# Teensy3.net
KiCad netlist of a schematic drawn in Altium Designer
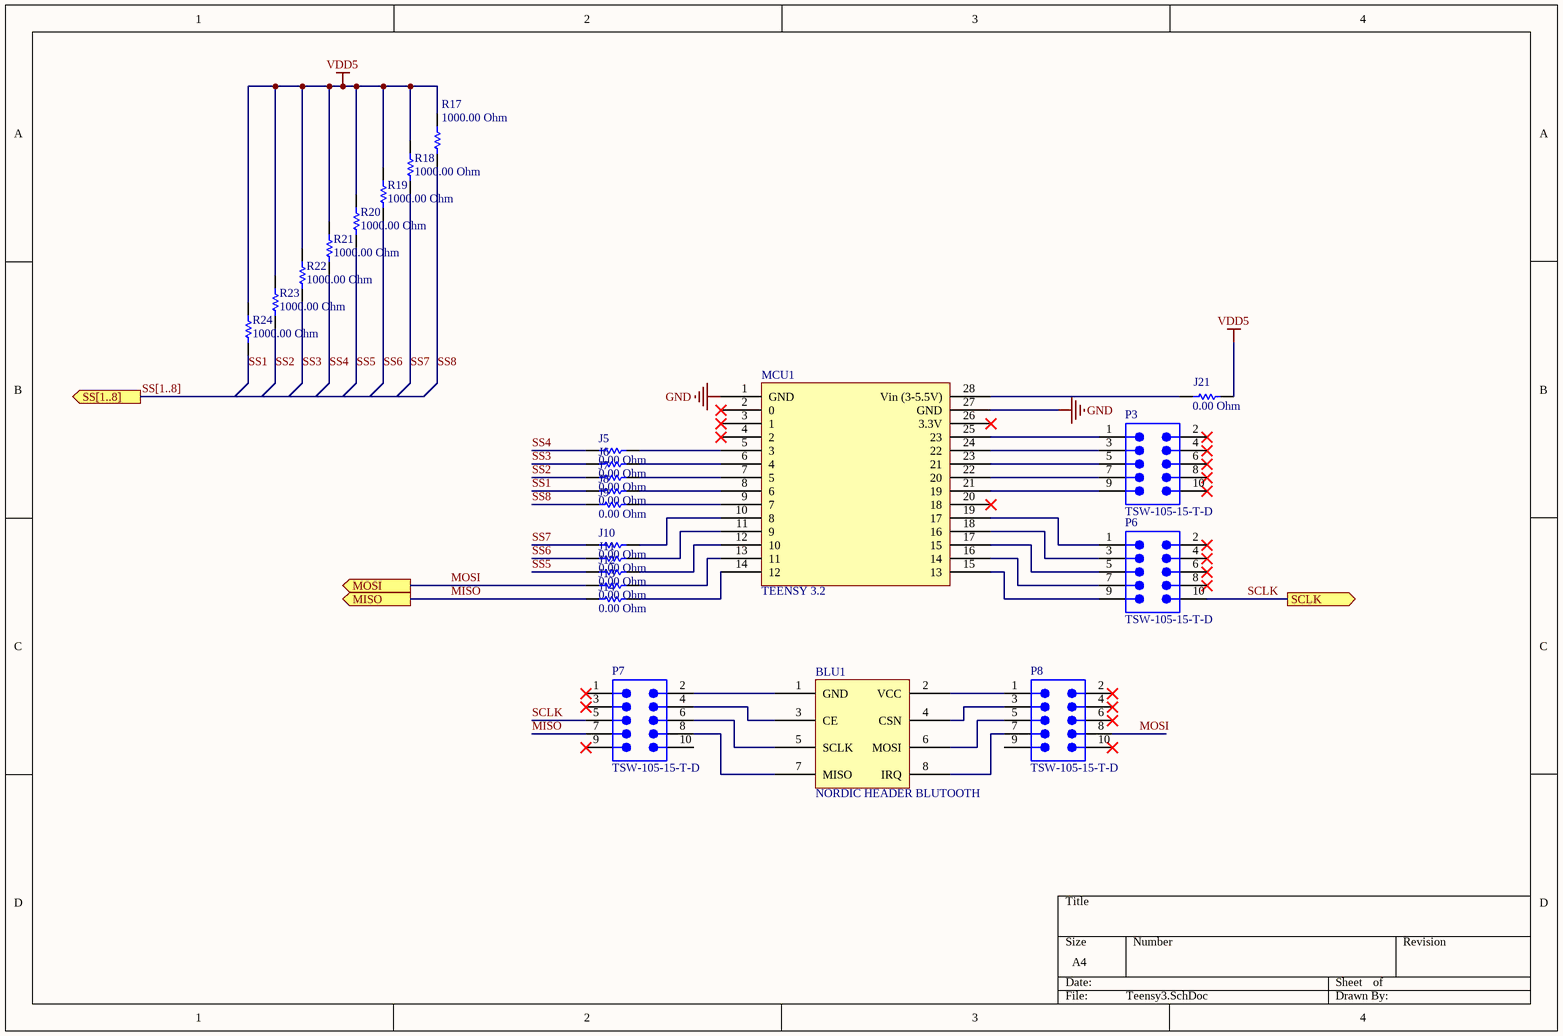
[diagram p0: Teensy3.SchDoc]

(export (version "E")
  (design (tool "Eeschema 10.0.6"))
  (components
    (comp (ref "BLU1")
      (value "NORDIC HEADER BLUTOOTH")
      (footprint "NORDIC BLUTOOTH HEADER")
      (description "BLUTOOTH MODULE")
      (fields (field (name "PUBLISHER") "Altium Limited"))
      (libsource (lib "AnserEMT") (part "NORDIC HEADER BLUTOOTH"))
    )
    (comp (ref "J5")
      (value "0.00 Ohm")
      (footprint "RESC1206(3216)_M")
      (description "Jumper 1206 (3216 Metric)")
      (fields (field (name "TOLERANCE") "None"))
      (libsource (lib "Altium Content Vault") (part "CMP-1014-00001-1"))
    )
    (comp (ref "J6")
      (value "0.00 Ohm")
      (footprint "RESC1206(3216)_M")
      (description "Jumper 1206 (3216 Metric)")
      (fields (field (name "TOLERANCE") "None"))
      (libsource (lib "Altium Content Vault") (part "CMP-1014-00001-1"))
    )
    (comp (ref "J7")
      (value "0.00 Ohm")
      (footprint "RESC1206(3216)_M")
      (description "Jumper 1206 (3216 Metric)")
      (fields (field (name "TOLERANCE") "None"))
      (libsource (lib "Altium Content Vault") (part "CMP-1014-00001-1"))
    )
    (comp (ref "J8")
      (value "0.00 Ohm")
      (footprint "RESC1206(3216)_M")
      (description "Jumper 1206 (3216 Metric)")
      (fields (field (name "TOLERANCE") "None"))
      (libsource (lib "Altium Content Vault") (part "CMP-1014-00001-1"))
    )
    (comp (ref "J9")
      (value "0.00 Ohm")
      (footprint "RESC1206(3216)_M")
      (description "Jumper 1206 (3216 Metric)")
      (fields (field (name "TOLERANCE") "None"))
      (libsource (lib "Altium Content Vault") (part "CMP-1014-00001-1"))
    )
    (comp (ref "J10")
      (value "0.00 Ohm")
      (footprint "RESC1206(3216)_M")
      (description "Jumper 1206 (3216 Metric)")
      (fields (field (name "TOLERANCE") "None"))
      (libsource (lib "Altium Content Vault") (part "CMP-1014-00001-1"))
    )
    (comp (ref "J11")
      (value "0.00 Ohm")
      (footprint "RESC1206(3216)_M")
      (description "Jumper 1206 (3216 Metric)")
      (fields (field (name "TOLERANCE") "None"))
      (libsource (lib "Altium Content Vault") (part "CMP-1014-00001-1"))
    )
    (comp (ref "J12")
      (value "0.00 Ohm")
      (footprint "RESC1206(3216)_M")
      (description "Jumper 1206 (3216 Metric)")
      (fields (field (name "TOLERANCE") "None"))
      (libsource (lib "Altium Content Vault") (part "CMP-1014-00001-1"))
    )
    (comp (ref "J13")
      (value "0.00 Ohm")
      (footprint "RESC1206(3216)_M")
      (description "Jumper 1206 (3216 Metric)")
      (fields (field (name "TOLERANCE") "None"))
      (libsource (lib "Altium Content Vault") (part "CMP-1014-00001-1"))
    )
    (comp (ref "J14")
      (value "0.00 Ohm")
      (footprint "RESC1206(3216)_M")
      (description "Jumper 1206 (3216 Metric)")
      (fields (field (name "TOLERANCE") "None"))
      (libsource (lib "Altium Content Vault") (part "CMP-1014-00001-1"))
    )
    (comp (ref "J21")
      (value "0.00 Ohm")
      (footprint "RESC1206(3216)_M")
      (description "Jumper 1206 (3216 Metric)")
      (fields (field (name "TOLERANCE") "None"))
      (libsource (lib "Altium Content Vault") (part "CMP-1014-00001-1"))
    )
    (comp (ref "MCU1")
      (value "TEENSY 3.2")
      (footprint "TEENSY 3.1")
      (description "MCU")
      (fields (field (name "PUBLISHER") "Altium Limited"))
      (libsource (lib "AnserEMT") (part "TEENSY 3.2"))
    )
    (comp (ref "P3")
      (value "TSW-105-15-T-D")
      (footprint "SMTC-TSW-105-15-X-D")
      (fields (field (name "MANUFACTURER") "Samtec"))
      (libsource (lib "Altium Content Vault") (part "CMP-1024-00368-1"))
    )
    (comp (ref "P6")
      (value "TSW-105-15-T-D")
      (footprint "SMTC-TSW-105-15-X-D")
      (fields (field (name "MANUFACTURER") "Samtec"))
      (libsource (lib "Altium Content Vault") (part "CMP-1024-00368-1"))
    )
    (comp (ref "P7")
      (value "TSW-105-15-T-D")
      (footprint "SMTC-TSW-105-15-X-D")
      (fields (field (name "MANUFACTURER") "Samtec"))
      (libsource (lib "Altium Content Vault") (part "CMP-1024-00368-1"))
    )
    (comp (ref "P8")
      (value "TSW-105-15-T-D")
      (footprint "SMTC-TSW-105-15-X-D")
      (fields (field (name "MANUFACTURER") "Samtec"))
      (libsource (lib "Altium Content Vault") (part "CMP-1024-00368-1"))
    )
    (comp (ref "R17")
      (value "1000.00 Ohm")
      (footprint "RESC0603(1608)_L")
      (description "1K 0.1W 5% 0603 (1608 Metric)  SMD")
      (fields (field (name "TOLERANCE") "5 %") (field (name "POWER") "0.1 W"))
      (libsource (lib "Altium Content Vault") (part "CMP-1012-00074-1"))
    )
    (comp (ref "R18")
      (value "1000.00 Ohm")
      (footprint "RESC0603(1608)_L")
      (description "1K 0.1W 5% 0603 (1608 Metric)  SMD")
      (fields (field (name "TOLERANCE") "5 %") (field (name "POWER") "0.1 W"))
      (libsource (lib "Altium Content Vault") (part "CMP-1012-00074-1"))
    )
    (comp (ref "R19")
      (value "1000.00 Ohm")
      (footprint "RESC0603(1608)_L")
      (description "1K 0.1W 5% 0603 (1608 Metric)  SMD")
      (fields (field (name "TOLERANCE") "5 %") (field (name "POWER") "0.1 W"))
      (libsource (lib "Altium Content Vault") (part "CMP-1012-00074-1"))
    )
    (comp (ref "R20")
      (value "1000.00 Ohm")
      (footprint "RESC0603(1608)_L")
      (description "1K 0.1W 5% 0603 (1608 Metric)  SMD")
      (fields (field (name "TOLERANCE") "5 %") (field (name "POWER") "0.1 W"))
      (libsource (lib "Altium Content Vault") (part "CMP-1012-00074-1"))
    )
    (comp (ref "R21")
      (value "1000.00 Ohm")
      (footprint "RESC0603(1608)_L")
      (description "1K 0.1W 5% 0603 (1608 Metric)  SMD")
      (fields (field (name "TOLERANCE") "5 %") (field (name "POWER") "0.1 W"))
      (libsource (lib "Altium Content Vault") (part "CMP-1012-00074-1"))
    )
    (comp (ref "R22")
      (value "1000.00 Ohm")
      (footprint "RESC0603(1608)_L")
      (description "1K 0.1W 5% 0603 (1608 Metric)  SMD")
      (fields (field (name "TOLERANCE") "5 %") (field (name "POWER") "0.1 W"))
      (libsource (lib "Altium Content Vault") (part "CMP-1012-00074-1"))
    )
    (comp (ref "R23")
      (value "1000.00 Ohm")
      (footprint "RESC0603(1608)_L")
      (description "1K 0.1W 5% 0603 (1608 Metric)  SMD")
      (fields (field (name "TOLERANCE") "5 %") (field (name "POWER") "0.1 W"))
      (libsource (lib "Altium Content Vault") (part "CMP-1012-00074-1"))
    )
    (comp (ref "R24")
      (value "1000.00 Ohm")
      (footprint "RESC0603(1608)_L")
      (description "1K 0.1W 5% 0603 (1608 Metric)  SMD")
      (fields (field (name "TOLERANCE") "5 %") (field (name "POWER") "0.1 W"))
      (libsource (lib "Altium Content Vault") (part "CMP-1012-00074-1"))
    )
  )
  (nets
    (net (code "1") (name "/MISO") (class "Default")
      (node (ref "J14") (pin "1") (pinfunction "1_1") (pintype "passive"))
      (node (ref "P7") (pin "7") (pinfunction "7_7") (pintype "passive"))
    )
    (net (code "2") (name "/MOSI") (class "Default")
      (node (ref "J13") (pin "1") (pinfunction "1_1") (pintype "passive"))
      (node (ref "P8") (pin "8") (pinfunction "8_8") (pintype "passive"))
    )
    (net (code "3") (name "/SCLK") (class "Default")
      (node (ref "P6") (pin "10") (pinfunction "10_10") (pintype "passive"))
      (node (ref "P7") (pin "5") (pinfunction "5_5") (pintype "passive"))
    )
    (net (code "4") (name "/SS1") (class "Default")
      (node (ref "J8") (pin "1") (pinfunction "1_1") (pintype "passive"))
      (node (ref "R24") (pin "2") (pinfunction "2_2") (pintype "passive"))
    )
    (net (code "5") (name "/SS2") (class "Default")
      (node (ref "J7") (pin "1") (pinfunction "1_1") (pintype "passive"))
      (node (ref "R23") (pin "2") (pinfunction "2_2") (pintype "passive"))
    )
    (net (code "6") (name "/SS3") (class "Default")
      (node (ref "J6") (pin "1") (pinfunction "1_1") (pintype "passive"))
      (node (ref "R22") (pin "2") (pinfunction "2_2") (pintype "passive"))
    )
    (net (code "7") (name "/SS4") (class "Default")
      (node (ref "J5") (pin "1") (pinfunction "1_1") (pintype "passive"))
      (node (ref "R21") (pin "2") (pinfunction "2_2") (pintype "passive"))
    )
    (net (code "8") (name "/SS5") (class "Default")
      (node (ref "J12") (pin "1") (pinfunction "1_1") (pintype "passive"))
      (node (ref "R20") (pin "2") (pinfunction "2_2") (pintype "passive"))
    )
    (net (code "9") (name "/SS6") (class "Default")
      (node (ref "J11") (pin "1") (pinfunction "1_1") (pintype "passive"))
      (node (ref "R19") (pin "2") (pinfunction "2_2") (pintype "passive"))
    )
    (net (code "10") (name "/SS7") (class "Default")
      (node (ref "J10") (pin "1") (pinfunction "1_1") (pintype "passive"))
      (node (ref "R18") (pin "2") (pinfunction "2_2") (pintype "passive"))
    )
    (net (code "11") (name "/SS8") (class "Default")
      (node (ref "J9") (pin "1") (pinfunction "1_1") (pintype "passive"))
      (node (ref "R17") (pin "2") (pinfunction "2_2") (pintype "passive"))
    )
    (net (code "13") (name "GND") (class "Default")
      (node (ref "MCU1") (pin "1") (pinfunction "GND_1") (pintype "passive"))
      (node (ref "MCU1") (pin "27") (pinfunction "GND_27") (pintype "passive"))
    )
    (net (code "14") (name "Net-(BLU1-CE)") (class "Default")
      (node (ref "BLU1") (pin "3") (pinfunction "CE_3") (pintype "passive"))
      (node (ref "P7") (pin "4") (pinfunction "4_4") (pintype "passive"))
    )
    (net (code "15") (name "Net-(BLU1-CSN)") (class "Default")
      (node (ref "BLU1") (pin "4") (pinfunction "CSN_4") (pintype "passive"))
      (node (ref "P8") (pin "3") (pinfunction "3_3") (pintype "passive"))
    )
    (net (code "16") (name "Net-(BLU1-GND)") (class "Default")
      (node (ref "BLU1") (pin "1") (pinfunction "GND_1") (pintype "passive"))
      (node (ref "P7") (pin "2") (pinfunction "2_2") (pintype "passive"))
    )
    (net (code "17") (name "Net-(BLU1-IRQ)") (class "Default")
      (node (ref "BLU1") (pin "8") (pinfunction "IRQ_8") (pintype "passive"))
      (node (ref "P8") (pin "7") (pinfunction "7_7") (pintype "passive"))
    )
    (net (code "18") (name "Net-(BLU1-MISO)") (class "Default")
      (node (ref "BLU1") (pin "7") (pinfunction "MISO_7") (pintype "passive"))
      (node (ref "P7") (pin "8") (pinfunction "8_8") (pintype "passive"))
    )
    (net (code "19") (name "Net-(BLU1-MOSI)") (class "Default")
      (node (ref "BLU1") (pin "6") (pinfunction "MOSI_6") (pintype "passive"))
      (node (ref "P8") (pin "5") (pinfunction "5_5") (pintype "passive"))
    )
    (net (code "20") (name "Net-(BLU1-SCLK)") (class "Default")
      (node (ref "BLU1") (pin "5") (pinfunction "SCLK_5") (pintype "passive"))
      (node (ref "P7") (pin "6") (pinfunction "6_6") (pintype "passive"))
    )
    (net (code "21") (name "Net-(BLU1-VCC)") (class "Default")
      (node (ref "BLU1") (pin "2") (pinfunction "VCC_2") (pintype "passive"))
      (node (ref "P8") (pin "1") (pinfunction "1_1") (pintype "passive"))
    )
    (net (code "22") (name "Net-(MCU1-3)") (class "Default")
      (node (ref "J5") (pin "2") (pinfunction "2_2") (pintype "passive"))
      (node (ref "MCU1") (pin "5") (pinfunction "3_5") (pintype "passive"))
    )
    (net (code "23") (name "Net-(MCU1-4)") (class "Default")
      (node (ref "J6") (pin "2") (pinfunction "2_2") (pintype "passive"))
      (node (ref "MCU1") (pin "6") (pinfunction "4_6") (pintype "passive"))
    )
    (net (code "24") (name "Net-(MCU1-5)") (class "Default")
      (node (ref "J7") (pin "2") (pinfunction "2_2") (pintype "passive"))
      (node (ref "MCU1") (pin "7") (pinfunction "5_7") (pintype "passive"))
    )
    (net (code "25") (name "Net-(MCU1-6)") (class "Default")
      (node (ref "J8") (pin "2") (pinfunction "2_2") (pintype "passive"))
      (node (ref "MCU1") (pin "8") (pinfunction "6_8") (pintype "passive"))
    )
    (net (code "26") (name "Net-(MCU1-7)") (class "Default")
      (node (ref "J9") (pin "2") (pinfunction "2_2") (pintype "passive"))
      (node (ref "MCU1") (pin "9") (pinfunction "7_9") (pintype "passive"))
    )
    (net (code "27") (name "Net-(MCU1-8)") (class "Default")
      (node (ref "J10") (pin "2") (pinfunction "2_2") (pintype "passive"))
      (node (ref "MCU1") (pin "10") (pinfunction "8_10") (pintype "passive"))
    )
    (net (code "28") (name "Net-(MCU1-9)") (class "Default")
      (node (ref "J11") (pin "2") (pinfunction "2_2") (pintype "passive"))
      (node (ref "MCU1") (pin "11") (pinfunction "9_11") (pintype "passive"))
    )
    (net (code "29") (name "Net-(MCU1-10)") (class "Default")
      (node (ref "J12") (pin "2") (pinfunction "2_2") (pintype "passive"))
      (node (ref "MCU1") (pin "12") (pinfunction "10_12") (pintype "passive"))
    )
    (net (code "30") (name "Net-(MCU1-11)") (class "Default")
      (node (ref "J13") (pin "2") (pinfunction "2_2") (pintype "passive"))
      (node (ref "MCU1") (pin "13") (pinfunction "11_13") (pintype "passive"))
    )
    (net (code "31") (name "Net-(MCU1-12)") (class "Default")
      (node (ref "J14") (pin "2") (pinfunction "2_2") (pintype "passive"))
      (node (ref "MCU1") (pin "14") (pinfunction "12_14") (pintype "passive"))
    )
    (net (code "32") (name "Net-(MCU1-13)") (class "Default")
      (node (ref "MCU1") (pin "15") (pinfunction "13_15") (pintype "passive"))
      (node (ref "P6") (pin "9") (pinfunction "9_9") (pintype "passive"))
    )
    (net (code "33") (name "Net-(MCU1-14)") (class "Default")
      (node (ref "MCU1") (pin "16") (pinfunction "14_16") (pintype "passive"))
      (node (ref "P6") (pin "7") (pinfunction "7_7") (pintype "passive"))
    )
    (net (code "34") (name "Net-(MCU1-15)") (class "Default")
      (node (ref "MCU1") (pin "17") (pinfunction "15_17") (pintype "passive"))
      (node (ref "P6") (pin "5") (pinfunction "5_5") (pintype "passive"))
    )
    (net (code "35") (name "Net-(MCU1-16)") (class "Default")
      (node (ref "MCU1") (pin "18") (pinfunction "16_18") (pintype "passive"))
      (node (ref "P6") (pin "3") (pinfunction "3_3") (pintype "passive"))
    )
    (net (code "36") (name "Net-(MCU1-17)") (class "Default")
      (node (ref "MCU1") (pin "19") (pinfunction "17_19") (pintype "passive"))
      (node (ref "P6") (pin "1") (pinfunction "1_1") (pintype "passive"))
    )
    (net (code "37") (name "Net-(MCU1-19)") (class "Default")
      (node (ref "MCU1") (pin "21") (pinfunction "19_21") (pintype "passive"))
      (node (ref "P3") (pin "9") (pinfunction "9_9") (pintype "passive"))
    )
    (net (code "38") (name "Net-(MCU1-20)") (class "Default")
      (node (ref "MCU1") (pin "22") (pinfunction "20_22") (pintype "passive"))
      (node (ref "P3") (pin "7") (pinfunction "7_7") (pintype "passive"))
    )
    (net (code "39") (name "Net-(MCU1-21)") (class "Default")
      (node (ref "MCU1") (pin "23") (pinfunction "21_23") (pintype "passive"))
      (node (ref "P3") (pin "5") (pinfunction "5_5") (pintype "passive"))
    )
    (net (code "40") (name "Net-(MCU1-22)") (class "Default")
      (node (ref "MCU1") (pin "24") (pinfunction "22_24") (pintype "passive"))
      (node (ref "P3") (pin "3") (pinfunction "3_3") (pintype "passive"))
    )
    (net (code "41") (name "Net-(MCU1-23)") (class "Default")
      (node (ref "MCU1") (pin "25") (pinfunction "23_25") (pintype "passive"))
      (node (ref "P3") (pin "1") (pinfunction "1_1") (pintype "passive"))
    )
    (net (code "42") (name "Net-(MCU1-Vin_(3-5.5V))") (class "Default")
      (node (ref "J21") (pin "1") (pinfunction "1_1") (pintype "passive"))
      (node (ref "MCU1") (pin "28") (pinfunction "Vin_(3-5.5V)_28") (pintype "passive"))
    )
    (net (code "43") (name "VDD5") (class "Default")
      (node (ref "J21") (pin "2") (pinfunction "2_2") (pintype "passive"))
      (node (ref "R17") (pin "1") (pinfunction "1_1") (pintype "passive"))
      (node (ref "R18") (pin "1") (pinfunction "1_1") (pintype "passive"))
      (node (ref "R19") (pin "1") (pinfunction "1_1") (pintype "passive"))
      (node (ref "R20") (pin "1") (pinfunction "1_1") (pintype "passive"))
      (node (ref "R21") (pin "1") (pinfunction "1_1") (pintype "passive"))
      (node (ref "R22") (pin "1") (pinfunction "1_1") (pintype "passive"))
      (node (ref "R23") (pin "1") (pinfunction "1_1") (pintype "passive"))
      (node (ref "R24") (pin "1") (pinfunction "1_1") (pintype "passive"))
    )
    (net (code "44") (name "unconnected-(MCU1-0-Pad2)") (class "Default")
      (node (ref "MCU1") (pin "2") (pinfunction "0_2") (pintype "passive+no_connect"))
    )
    (net (code "45") (name "unconnected-(MCU1-1-Pad3)") (class "Default")
      (node (ref "MCU1") (pin "3") (pinfunction "1_3") (pintype "passive+no_connect"))
    )
    (net (code "46") (name "unconnected-(MCU1-2-Pad4)") (class "Default")
      (node (ref "MCU1") (pin "4") (pinfunction "2_4") (pintype "passive+no_connect"))
    )
    (net (code "47") (name "unconnected-(MCU1-3.3V-Pad26)") (class "Default")
      (node (ref "MCU1") (pin "26") (pinfunction "3.3V_26") (pintype "passive+no_connect"))
    )
    (net (code "48") (name "unconnected-(MCU1-18-Pad20)") (class "Default")
      (node (ref "MCU1") (pin "20") (pinfunction "18_20") (pintype "passive+no_connect"))
    )
    (net (code "49") (name "unconnected-(P3-Pad2)") (class "Default")
      (node (ref "P3") (pin "2") (pinfunction "2_2") (pintype "passive+no_connect"))
    )
    (net (code "50") (name "unconnected-(P3-Pad4)") (class "Default")
      (node (ref "P3") (pin "4") (pinfunction "4_4") (pintype "passive+no_connect"))
    )
    (net (code "51") (name "unconnected-(P3-Pad6)") (class "Default")
      (node (ref "P3") (pin "6") (pinfunction "6_6") (pintype "passive+no_connect"))
    )
    (net (code "52") (name "unconnected-(P3-Pad8)") (class "Default")
      (node (ref "P3") (pin "8") (pinfunction "8_8") (pintype "passive+no_connect"))
    )
    (net (code "53") (name "unconnected-(P3-Pad10)") (class "Default")
      (node (ref "P3") (pin "10") (pinfunction "10_10") (pintype "passive+no_connect"))
    )
    (net (code "54") (name "unconnected-(P6-Pad2)") (class "Default")
      (node (ref "P6") (pin "2") (pinfunction "2_2") (pintype "passive+no_connect"))
    )
    (net (code "55") (name "unconnected-(P6-Pad4)") (class "Default")
      (node (ref "P6") (pin "4") (pinfunction "4_4") (pintype "passive+no_connect"))
    )
    (net (code "56") (name "unconnected-(P6-Pad6)") (class "Default")
      (node (ref "P6") (pin "6") (pinfunction "6_6") (pintype "passive+no_connect"))
    )
    (net (code "57") (name "unconnected-(P6-Pad8)") (class "Default")
      (node (ref "P6") (pin "8") (pinfunction "8_8") (pintype "passive+no_connect"))
    )
    (net (code "58") (name "unconnected-(P7-Pad1)") (class "Default")
      (node (ref "P7") (pin "1") (pinfunction "1_1") (pintype "passive+no_connect"))
    )
    (net (code "59") (name "unconnected-(P7-Pad3)") (class "Default")
      (node (ref "P7") (pin "3") (pinfunction "3_3") (pintype "passive+no_connect"))
    )
    (net (code "60") (name "unconnected-(P7-Pad9)") (class "Default")
      (node (ref "P7") (pin "9") (pinfunction "9_9") (pintype "passive+no_connect"))
    )
    (net (code "61") (name "unconnected-(P7-Pad10)") (class "Default")
      (node (ref "P7") (pin "10") (pinfunction "10_10") (pintype "passive"))
    )
    (net (code "62") (name "unconnected-(P8-Pad2)") (class "Default")
      (node (ref "P8") (pin "2") (pinfunction "2_2") (pintype "passive+no_connect"))
    )
    (net (code "63") (name "unconnected-(P8-Pad4)") (class "Default")
      (node (ref "P8") (pin "4") (pinfunction "4_4") (pintype "passive+no_connect"))
    )
    (net (code "64") (name "unconnected-(P8-Pad6)") (class "Default")
      (node (ref "P8") (pin "6") (pinfunction "6_6") (pintype "passive+no_connect"))
    )
    (net (code "65") (name "unconnected-(P8-Pad9)") (class "Default")
      (node (ref "P8") (pin "9") (pinfunction "9_9") (pintype "passive"))
    )
    (net (code "66") (name "unconnected-(P8-Pad10)") (class "Default")
      (node (ref "P8") (pin "10") (pinfunction "10_10") (pintype "passive+no_connect"))
    )
  )
)
